# InterfacesB_NONISO422a.net
KiCad netlist of a schematic drawn in Altium Designer
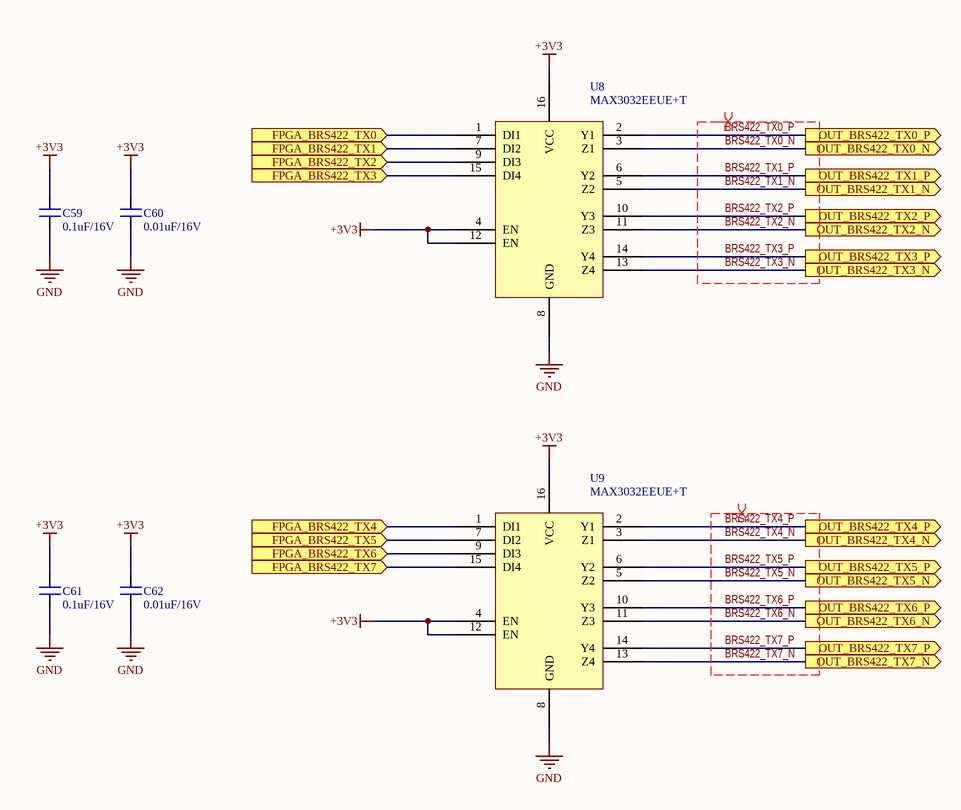
[diagram p0: InterfacesB_NONISO422a.SchDoc]

(export (version "E")
  (design (tool "Eeschema 10.0.6"))
  (components
    (comp (ref "C59")
      (value "0.1uF/16V")
      (footprint "CAP_0805")
      (fields (field (name "Comment") "CAP_0805"))
      (libsource (lib "AdapterLib") (part "CAP_0805"))
    )
    (comp (ref "C60")
      (value "0.01uF/16V")
      (footprint "CAP_0805")
      (fields (field (name "Comment") "CAP_0805"))
      (libsource (lib "AdapterLib") (part "CAP_0805"))
    )
    (comp (ref "C61")
      (value "0.1uF/16V")
      (footprint "CAP_0805")
      (fields (field (name "Comment") "CAP_0805"))
      (libsource (lib "AdapterLib") (part "CAP_0805"))
    )
    (comp (ref "C62")
      (value "0.01uF/16V")
      (footprint "CAP_0805")
      (fields (field (name "Comment") "CAP_0805"))
      (libsource (lib "AdapterLib") (part "CAP_0805"))
    )
    (comp (ref "U8")
      (value "MAX3032EEUE+T")
      (footprint "MAX3032EEUE+T")
      (libsource (lib "AdapterLib") (part "MAX3032EEUE+T"))
    )
    (comp (ref "U9")
      (value "MAX3032EEUE+T")
      (footprint "MAX3032EEUE+T")
      (libsource (lib "AdapterLib") (part "MAX3032EEUE+T"))
    )
  )
  (nets
    (net (code "1") (name "+3V3") (class "Default")
      (node (ref "C59") (pin "1") (pinfunction "1_1") (pintype "passive"))
      (node (ref "C60") (pin "1") (pinfunction "1_1") (pintype "passive"))
      (node (ref "C61") (pin "1") (pinfunction "1_1") (pintype "passive"))
      (node (ref "C62") (pin "1") (pinfunction "1_1") (pintype "passive"))
      (node (ref "U8") (pin "12") (pinfunction "EN_12") (pintype "passive"))
      (node (ref "U8") (pin "16") (pinfunction "VCC_16") (pintype "passive"))
      (node (ref "U8") (pin "4") (pinfunction "EN_4") (pintype "passive"))
      (node (ref "U9") (pin "12") (pinfunction "EN_12") (pintype "passive"))
      (node (ref "U9") (pin "16") (pinfunction "VCC_16") (pintype "passive"))
      (node (ref "U9") (pin "4") (pinfunction "EN_4") (pintype "passive"))
    )
    (net (code "2") (name "/BRS422_TX0_N") (class "Default")
      (node (ref "U8") (pin "3") (pinfunction "Z1_3") (pintype "passive"))
    )
    (net (code "3") (name "/BRS422_TX0_P") (class "Default")
      (node (ref "U8") (pin "2") (pinfunction "Y1_2") (pintype "passive"))
    )
    (net (code "4") (name "/BRS422_TX1_N") (class "Default")
      (node (ref "U8") (pin "5") (pinfunction "Z2_5") (pintype "passive"))
    )
    (net (code "5") (name "/BRS422_TX1_P") (class "Default")
      (node (ref "U8") (pin "6") (pinfunction "Y2_6") (pintype "passive"))
    )
    (net (code "6") (name "/BRS422_TX2_N") (class "Default")
      (node (ref "U8") (pin "11") (pinfunction "Z3_11") (pintype "passive"))
    )
    (net (code "7") (name "/BRS422_TX2_P") (class "Default")
      (node (ref "U8") (pin "10") (pinfunction "Y3_10") (pintype "passive"))
    )
    (net (code "8") (name "/BRS422_TX3_N") (class "Default")
      (node (ref "U8") (pin "13") (pinfunction "Z4_13") (pintype "passive"))
    )
    (net (code "9") (name "/BRS422_TX3_P") (class "Default")
      (node (ref "U8") (pin "14") (pinfunction "Y4_14") (pintype "passive"))
    )
    (net (code "10") (name "/BRS422_TX4_N") (class "Default")
      (node (ref "U9") (pin "3") (pinfunction "Z1_3") (pintype "passive"))
    )
    (net (code "11") (name "/BRS422_TX4_P") (class "Default")
      (node (ref "U9") (pin "2") (pinfunction "Y1_2") (pintype "passive"))
    )
    (net (code "12") (name "/BRS422_TX5_N") (class "Default")
      (node (ref "U9") (pin "5") (pinfunction "Z2_5") (pintype "passive"))
    )
    (net (code "13") (name "/BRS422_TX5_P") (class "Default")
      (node (ref "U9") (pin "6") (pinfunction "Y2_6") (pintype "passive"))
    )
    (net (code "14") (name "/BRS422_TX6_N") (class "Default")
      (node (ref "U9") (pin "11") (pinfunction "Z3_11") (pintype "passive"))
    )
    (net (code "15") (name "/BRS422_TX6_P") (class "Default")
      (node (ref "U9") (pin "10") (pinfunction "Y3_10") (pintype "passive"))
    )
    (net (code "16") (name "/BRS422_TX7_N") (class "Default")
      (node (ref "U9") (pin "13") (pinfunction "Z4_13") (pintype "passive"))
    )
    (net (code "17") (name "/BRS422_TX7_P") (class "Default")
      (node (ref "U9") (pin "14") (pinfunction "Y4_14") (pintype "passive"))
    )
    (net (code "18") (name "/FPGA_BRS422_TX0") (class "Default")
      (node (ref "U8") (pin "1") (pinfunction "DI1_1") (pintype "passive"))
    )
    (net (code "19") (name "/FPGA_BRS422_TX1") (class "Default")
      (node (ref "U8") (pin "7") (pinfunction "DI2_7") (pintype "passive"))
    )
    (net (code "20") (name "/FPGA_BRS422_TX2") (class "Default")
      (node (ref "U8") (pin "9") (pinfunction "DI3_9") (pintype "passive"))
    )
    (net (code "21") (name "/FPGA_BRS422_TX3") (class "Default")
      (node (ref "U8") (pin "15") (pinfunction "DI4_15") (pintype "passive"))
    )
    (net (code "22") (name "/FPGA_BRS422_TX4") (class "Default")
      (node (ref "U9") (pin "1") (pinfunction "DI1_1") (pintype "passive"))
    )
    (net (code "23") (name "/FPGA_BRS422_TX5") (class "Default")
      (node (ref "U9") (pin "7") (pinfunction "DI2_7") (pintype "passive"))
    )
    (net (code "24") (name "/FPGA_BRS422_TX6") (class "Default")
      (node (ref "U9") (pin "9") (pinfunction "DI3_9") (pintype "passive"))
    )
    (net (code "25") (name "/FPGA_BRS422_TX7") (class "Default")
      (node (ref "U9") (pin "15") (pinfunction "DI4_15") (pintype "passive"))
    )
    (net (code "26") (name "GND") (class "Default")
      (node (ref "C59") (pin "2") (pinfunction "2_2") (pintype "passive"))
      (node (ref "C60") (pin "2") (pinfunction "2_2") (pintype "passive"))
      (node (ref "C61") (pin "2") (pinfunction "2_2") (pintype "passive"))
      (node (ref "C62") (pin "2") (pinfunction "2_2") (pintype "passive"))
      (node (ref "U8") (pin "8") (pinfunction "GND_8") (pintype "passive"))
      (node (ref "U9") (pin "8") (pinfunction "GND_8") (pintype "passive"))
    )
  )
)
